# Sheet3_MCU.net
KiCad netlist of a schematic drawn in Altium Designer
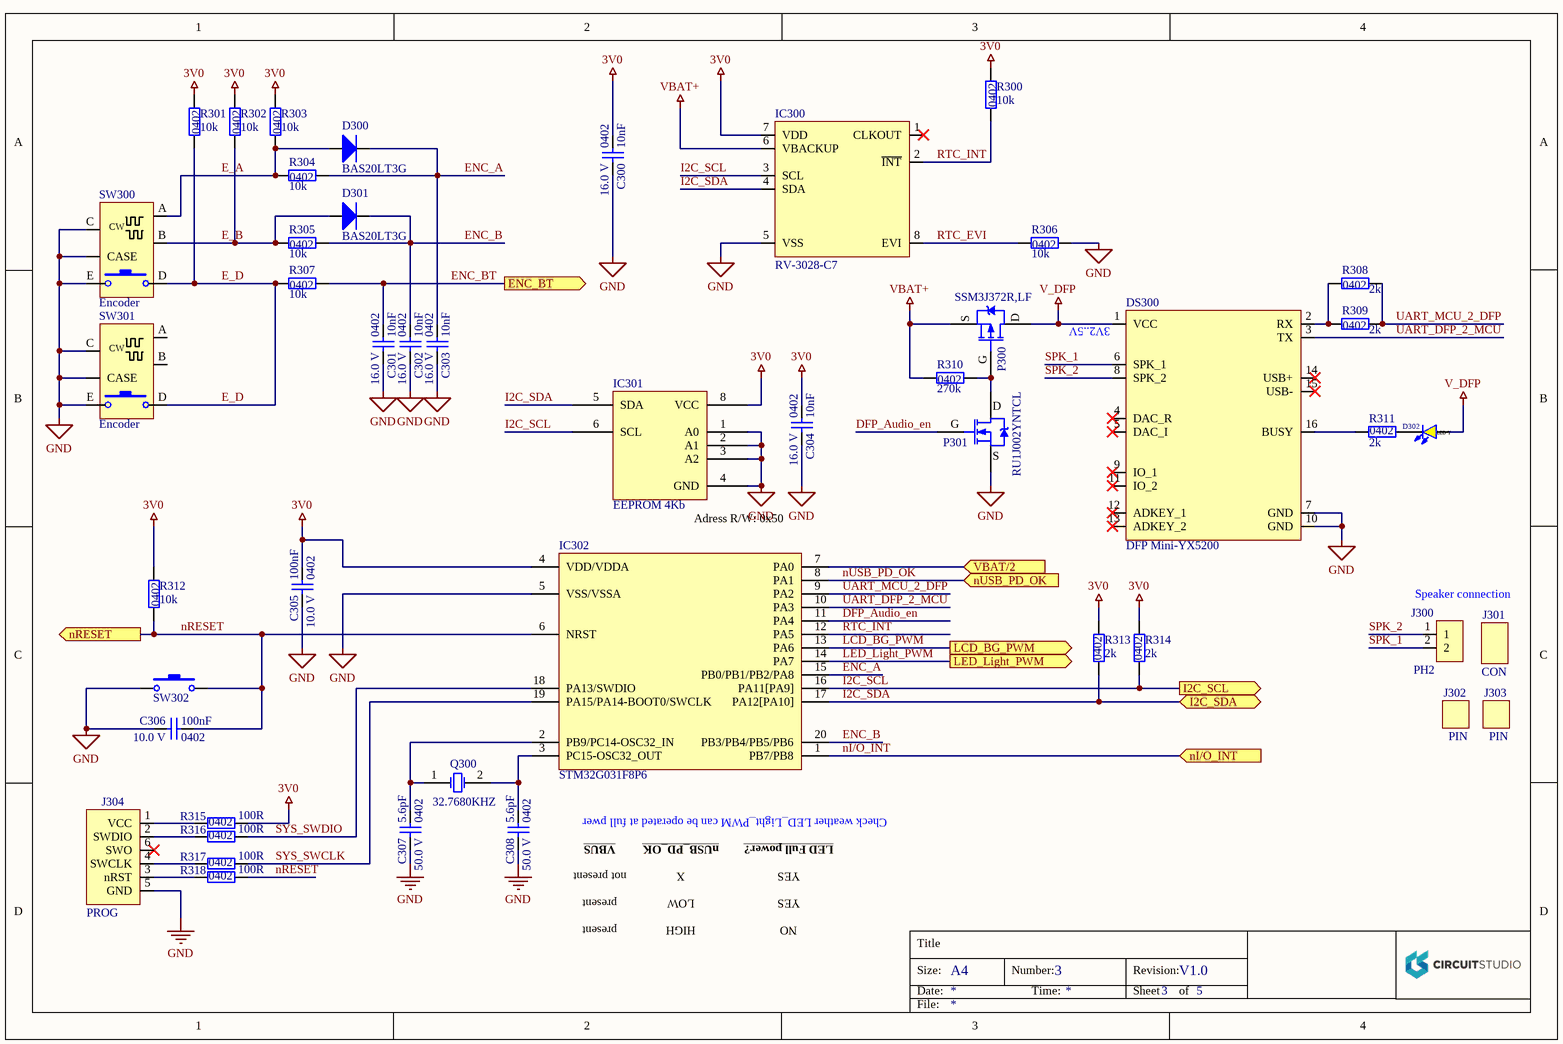
[diagram p0: Sheet3_MCU.SchDoc]

(export (version "E")
  (design (tool "Eeschema 10.0.6"))
  (components
    (comp (ref "C300")
      (value "C 10nF 0402 16V")
      (footprint "0402")
      (description "CAP CER 10000PF 16V Y5V 0402")
      (fields
        (field (name "MANUFACTURER") "Samsung Electro-Mechanics")
        (field (name "MANUFACTURER PART NUMBER") "CL05F103ZO5NNNC")
        (field (name "CAPACITANCE") "10nF")
        (field (name "VOLTAGE") "16.0 V")
      )
      (libsource (lib "CS_Part_Library") (part "CAP_10nF_16V_0402"))
    )
    (comp (ref "C301")
      (value "C 10nF 0402 16V")
      (footprint "0402")
      (description "CAP CER 10000PF 16V Y5V 0402")
      (fields
        (field (name "MANUFACTURER") "Samsung Electro-Mechanics")
        (field (name "MANUFACTURER PART NUMBER") "CL05F103ZO5NNNC")
        (field (name "CAPACITANCE") "10nF")
        (field (name "VOLTAGE") "16.0 V")
      )
      (libsource (lib "CS_Part_Library") (part "CAP_10nF_16V_0402"))
    )
    (comp (ref "C302")
      (value "C 10nF 0402 16V")
      (footprint "0402")
      (description "CAP CER 10000PF 16V Y5V 0402")
      (fields
        (field (name "MANUFACTURER") "Samsung Electro-Mechanics")
        (field (name "MANUFACTURER PART NUMBER") "CL05F103ZO5NNNC")
        (field (name "CAPACITANCE") "10nF")
        (field (name "VOLTAGE") "16.0 V")
      )
      (libsource (lib "CS_Part_Library") (part "CAP_10nF_16V_0402"))
    )
    (comp (ref "C303")
      (value "C 10nF 0402 16V")
      (footprint "0402")
      (description "CAP CER 10000PF 16V Y5V 0402")
      (fields
        (field (name "MANUFACTURER") "Samsung Electro-Mechanics")
        (field (name "MANUFACTURER PART NUMBER") "CL05F103ZO5NNNC")
        (field (name "CAPACITANCE") "10nF")
        (field (name "VOLTAGE") "16.0 V")
      )
      (libsource (lib "CS_Part_Library") (part "CAP_10nF_16V_0402"))
    )
    (comp (ref "C304")
      (value "C 10nF 0402 16V")
      (footprint "0402")
      (description "CAP CER 10000PF 16V Y5V 0402")
      (fields
        (field (name "MANUFACTURER") "Samsung Electro-Mechanics")
        (field (name "MANUFACTURER PART NUMBER") "CL05F103ZO5NNNC")
        (field (name "CAPACITANCE") "10nF")
        (field (name "VOLTAGE") "16.0 V")
      )
      (libsource (lib "CS_Part_Library") (part "CAP_10nF_16V_0402"))
    )
    (comp (ref "C305")
      (value "C 100nF 0402 10V")
      (footprint "0402")
      (description "CAP CER 0.1UF 10V X5R 0402")
      (fields
        (field (name "MANUFACTURER") "Samsung Electro-Mechanics")
        (field (name "MANUFACTURER PART NUMBER") "CL05A104MP5NNNC")
        (field (name "CAPACITANCE") "100nF")
        (field (name "VOLTAGE") "10.0 V")
      )
      (libsource (lib "CS_Part_Library") (part "CAP_100nF_10V_0402"))
    )
    (comp (ref "C306")
      (value "C 100nF 0402 10V")
      (footprint "0402")
      (description "CAP CER 0.1UF 10V X5R 0402")
      (fields
        (field (name "MANUFACTURER") "Samsung Electro-Mechanics")
        (field (name "MANUFACTURER PART NUMBER") "CL05A104MP5NNNC")
        (field (name "CAPACITANCE") "100nF")
        (field (name "VOLTAGE") "10.0 V")
      )
      (libsource (lib "CS_Part_Library") (part "CAP_100nF_10V_0402"))
    )
    (comp (ref "C307")
      (value "C 5.6pF 0402 50V")
      (footprint "0402")
      (description "CAP CER 5.6PF 50V C0G/NP0 0402")
      (fields
        (field (name "MANUFACTURER") "Samsung Electro-Mechanics")
        (field (name "MANUFACTURER PART NUMBER") "CL05C5R6DB5NNNC")
        (field (name "CAPACITANCE") "5.6pF")
        (field (name "VOLTAGE") "50.0 V")
      )
      (libsource (lib "CS_Part_Library") (part "CAP_5.6PF_50V_0402"))
    )
    (comp (ref "C308")
      (value "C 5.6pF 0402 50V")
      (footprint "0402")
      (description "CAP CER 5.6PF 50V C0G/NP0 0402")
      (fields
        (field (name "MANUFACTURER") "Samsung Electro-Mechanics")
        (field (name "MANUFACTURER PART NUMBER") "CL05C5R6DB5NNNC")
        (field (name "CAPACITANCE") "5.6pF")
        (field (name "VOLTAGE") "50.0 V")
      )
      (libsource (lib "CS_Part_Library") (part "CAP_5.6PF_50V_0402"))
    )
    (comp (ref "D300")
      (value "BAS20LT3G")
      (footprint "SOT-23-3")
      (description "DIODE GP 200V 200MA SOT23-3")
      (fields (field (name "MANUFACTURER") "onsemi") (field (name "MANUFACTURER PART NUMBER") "BAS20LT3G"))
      (libsource (lib "Symbols") (part "D_LL_200V_200mA"))
    )
    (comp (ref "D301")
      (value "BAS20LT3G")
      (footprint "SOT-23-3")
      (description "DIODE GP 200V 200MA SOT23-3")
      (fields (field (name "MANUFACTURER") "onsemi") (field (name "MANUFACTURER PART NUMBER") "BAS20LT3G"))
      (libsource (lib "Symbols") (part "D_LL_200V_200mA"))
    )
    (comp (ref "D302")
      (value "LED Y")
      (footprint "LED_0603")
      (description "LED YELLOW DIFFUSED")
      (fields
        (field (name "MANUFACTURER") "Stanley Electric Co")
        (field (name "MANUFACTURER PART NUMBER") "FKY1111C-TR")
      )
      (libsource (lib "CS_Part_Library") (part "D_LED_Yellow_0603"))
    )
    (comp (ref "DS300")
      (value "DFP Mini-YX5200")
      (footprint "DFP_Player_Mini")
      (description "Mini-YX5200 Audio MP3 Modul")
      (fields (field (name "MANUFACTURER") "DFRobot") (field (name "MANUFACTURER PART NUMBER") "DFR0299"))
      (libsource (lib "CS_Part_Library") (part "DFP_Player_mini"))
    )
    (comp (ref "IC300")
      (value "RV-3028-C7")
      (footprint "MC-C7")
      (description "IC RTC CLK/CALENDAR I2C 10SON")
      (fields
        (field (name "MANUFACTURER") "Micro Crystal AG")
        (field (name "MANUFACTURER PART NUMBER") "RV-3028-C7TAQC")
      )
      (libsource (lib "Symbols") (part "IC_RTC_3028-C7"))
    )
    (comp (ref "IC301")
      (value "EEPROM 4Kb")
      (footprint "TSSOP-8_4.4mm")
      (description "IC EEPROM 4KBIT I2C 1MHZ 8TSSOP")
      (fields
        (field (name "MANUFACTURER") "Microchip Technology")
        (field (name "MANUFACTURER PART NUMBER") "AT34C04-X5M-T")
      )
      (libsource (lib "CS_Part_Library") (part "IC_EEPROM_4Kb"))
    )
    (comp (ref "IC302")
      (value "STM32G031F8P6")
      (footprint "TSSOP-20")
      (description "IC MCU 32BIT 32KB FLASH 20TSSOP")
      (fields (field (name "MANUFACTURER") "STMicroelectronics"))
      (libsource (lib "CS_Part_Library") (part "IC_MCU_STM32G031F8P6"))
    )
    (comp (ref "J300")
      (value "PH2")
      (footprint "J_S2B-PH-K-S")
      (description "CONN HEADER R/A 2POS 2MM")
      (fields
        (field (name "MANUFACTURER") "JST Sales America Inc.")
        (field (name "MANUFACTURER PART NUMBER") "S2B-PH-KL(LF)(SN)")
      )
      (libsource (lib "Symbols") (part "J_S2B-PH-KL"))
    )
    (comp (ref "J301")
      (value "CON")
      (description "CONN CONNECTOR PH 2POS 2MM")
      (fields
        (field (name "MANUFACTURER") "JST Sales America Inc.")
        (field (name "MANUFACTURER PART NUMBER") "PHR-2-R")
      )
      (libsource (lib "Symbols") (part "J_PHR-2-R"))
    )
    (comp (ref "J302")
      (value "PIN")
      (description "PIN INSERT")
      (fields
        (field (name "MANUFACTURER") "JST Sales America Inc.")
        (field (name "MANUFACTURER PART NUMBER") "SPH-004T-P0.5S")
      )
      (libsource (lib "Symbols") (part "J_PHR-2-R_PIN"))
    )
    (comp (ref "J303")
      (value "PIN")
      (description "PIN INSERT")
      (fields
        (field (name "MANUFACTURER") "JST Sales America Inc.")
        (field (name "MANUFACTURER PART NUMBER") "SPH-004T-P0.5S")
      )
      (libsource (lib "Symbols") (part "J_PHR-2-R_PIN"))
    )
    (comp (ref "J304")
      (value "PROG")
      (footprint "J_TC2030-IDC-NL")
      (description "SWD Programmer No Legs")
      (fields (field (name "MANUFACTURER") "Tag_connect") (field (name "MANUFACTURER PART NUMBER") "TC2030"))
      (libsource (lib "CS_Part_Library") (part "J_TC2030-IDC-NL"))
    )
    (comp (ref "P300")
      (value "P PMOS 30V 6A")
      (footprint "SOT-23-3-F")
      (description "MOSFET P-CH 30V 6A SOT23F")
      (fields
        (field (name "MANUFACTURER") "Toshiba Semiconductor and Storage")
        (field (name "MANUFACTURER PART NUMBER") "SSM3J372R,LF")
      )
      (libsource (lib "CS_Part_Library") (part "P_PCH_30V_1W"))
    )
    (comp (ref "P301")
      (value "P_NCH_50V_150mW")
      (footprint "UMT3F")
      (description "MOSFET N-CH 50V 200MA UMT3F")
      (fields
        (field (name "MANUFACTURER") "Rohm Semiconductor")
        (field (name "MANUFACTURER PART NUMBER") "RU1J002YNTCL")
      )
      (libsource (lib "CS_Part_Library") (part "P_NCH_50V_150mW"))
    )
    (comp (ref "Q300")
      (value "32.7680KHZ")
      (footprint "Q2_3.2x1.5")
      (description "CRYSTAL 32.7680KHZ 12.5PF SMD")
      (fields
        (field (name "MANUFACTURER") "NDK America, Inc.")
        (field (name "MANUFACTURER PART NUMBER") "NX3215SA-32.768K-EXS00A-MU00003")
      )
      (libsource (lib "CS_Part_Library") (part "Q_32k768_12p5"))
    )
    (comp (ref "R300")
      (value "R 10k 0402")
      (footprint "0402")
      (description "RES 10K OHM 1% 1/16W 0402")
      (fields
        (field (name "MANUFACTURER") "YAGEO")
        (field (name "MANUFACTURER PART NUMBER") "RC0402FR-0710KL")
        (field (name "RESISTANCE") "10k")
      )
      (libsource (lib "CS_Part_Library") (part "R_10k_0402"))
    )
    (comp (ref "R301")
      (value "R 10k 0402")
      (footprint "0402")
      (description "RES 10K OHM 1% 1/16W 0402")
      (fields
        (field (name "MANUFACTURER") "YAGEO")
        (field (name "MANUFACTURER PART NUMBER") "RC0402FR-0710KL")
        (field (name "RESISTANCE") "10k")
      )
      (libsource (lib "CS_Part_Library") (part "R_10k_0402"))
    )
    (comp (ref "R302")
      (value "R 10k 0402")
      (footprint "0402")
      (description "RES 10K OHM 1% 1/16W 0402")
      (fields
        (field (name "MANUFACTURER") "YAGEO")
        (field (name "MANUFACTURER PART NUMBER") "RC0402FR-0710KL")
        (field (name "RESISTANCE") "10k")
      )
      (libsource (lib "CS_Part_Library") (part "R_10k_0402"))
    )
    (comp (ref "R303")
      (value "R 10k 0402")
      (footprint "0402")
      (description "RES 10K OHM 1% 1/16W 0402")
      (fields
        (field (name "MANUFACTURER") "YAGEO")
        (field (name "MANUFACTURER PART NUMBER") "RC0402FR-0710KL")
        (field (name "RESISTANCE") "10k")
      )
      (libsource (lib "CS_Part_Library") (part "R_10k_0402"))
    )
    (comp (ref "R304")
      (value "R 10k 0402")
      (footprint "0402")
      (description "RES 10K OHM 1% 1/16W 0402")
      (fields
        (field (name "MANUFACTURER") "YAGEO")
        (field (name "MANUFACTURER PART NUMBER") "RC0402FR-0710KL")
        (field (name "RESISTANCE") "10k")
      )
      (libsource (lib "") (part "R_10k_0402_1"))
    )
    (comp (ref "R305")
      (value "R 10k 0402")
      (footprint "0402")
      (description "RES 10K OHM 1% 1/16W 0402")
      (fields
        (field (name "MANUFACTURER") "YAGEO")
        (field (name "MANUFACTURER PART NUMBER") "RC0402FR-0710KL")
        (field (name "RESISTANCE") "10k")
      )
      (libsource (lib "") (part "R_10k_0402_1"))
    )
    (comp (ref "R306")
      (value "R 10k 0402")
      (footprint "0402")
      (description "RES 10K OHM 1% 1/16W 0402")
      (fields
        (field (name "MANUFACTURER") "YAGEO")
        (field (name "MANUFACTURER PART NUMBER") "RC0402FR-0710KL")
        (field (name "RESISTANCE") "10k")
      )
      (libsource (lib "") (part "R_10k_0402_1"))
    )
    (comp (ref "R307")
      (value "R 10k 0402")
      (footprint "0402")
      (description "RES 10K OHM 1% 1/16W 0402")
      (fields
        (field (name "MANUFACTURER") "YAGEO")
        (field (name "MANUFACTURER PART NUMBER") "RC0402FR-0710KL")
        (field (name "RESISTANCE") "10k")
      )
      (libsource (lib "") (part "R_10k_0402_1"))
    )
    (comp (ref "R308")
      (value "R 2k 0402")
      (footprint "0402")
      (description "RES 2K OHM 1% 1/16W 0402")
      (fields
        (field (name "MANUFACTURER") "Stackpole Electronics Inc")
        (field (name "MANUFACTURER PART NUMBER") "RMCF0402FT2K00")
        (field (name "RESISTANCE") "2k")
      )
      (libsource (lib "CS_Part_Library") (part "R_2k_0402"))
    )
    (comp (ref "R309")
      (value "R 2k 0402")
      (footprint "0402")
      (description "RES 2K OHM 1% 1/16W 0402")
      (fields
        (field (name "MANUFACTURER") "Stackpole Electronics Inc")
        (field (name "MANUFACTURER PART NUMBER") "RMCF0402FT2K00")
        (field (name "RESISTANCE") "2k")
      )
      (libsource (lib "CS_Part_Library") (part "R_2k_0402"))
    )
    (comp (ref "R310")
      (value "R 270k 0402")
      (footprint "0402")
      (description "RES 270K OHM 1% 1/16W 0402")
      (fields
        (field (name "MANUFACTURER") "YAGEO")
        (field (name "MANUFACTURER PART NUMBER") "RC0402FR-07270KL")
        (field (name "RESISTANCE") "270k")
      )
      (libsource (lib "CS_Part_Library") (part "R_270k_0402"))
    )
    (comp (ref "R311")
      (value "R 2k 0402")
      (footprint "0402")
      (description "RES 2K OHM 1% 1/16W 0402")
      (fields
        (field (name "MANUFACTURER") "Stackpole Electronics Inc")
        (field (name "MANUFACTURER PART NUMBER") "RMCF0402FT2K00")
        (field (name "RESISTANCE") "2k")
      )
      (libsource (lib "") (part "R_2k_0402_1"))
    )
    (comp (ref "R312")
      (value "R 10k 0402")
      (footprint "0402")
      (description "RES 10K OHM 1% 1/16W 0402")
      (fields
        (field (name "MANUFACTURER") "YAGEO")
        (field (name "MANUFACTURER PART NUMBER") "RC0402FR-0710KL")
        (field (name "RESISTANCE") "10k")
      )
      (libsource (lib "CS_Part_Library") (part "R_10k_0402"))
    )
    (comp (ref "R313")
      (value "R 2k 0402")
      (footprint "0402")
      (description "RES 2K OHM 1% 1/16W 0402")
      (fields
        (field (name "MANUFACTURER") "Stackpole Electronics Inc")
        (field (name "MANUFACTURER PART NUMBER") "RMCF0402FT2K00")
        (field (name "RESISTANCE") "2k")
      )
      (libsource (lib "") (part "R_2k_0402_2"))
    )
    (comp (ref "R314")
      (value "R 2k 0402")
      (footprint "0402")
      (description "RES 2K OHM 1% 1/16W 0402")
      (fields
        (field (name "MANUFACTURER") "Stackpole Electronics Inc")
        (field (name "MANUFACTURER PART NUMBER") "RMCF0402FT2K00")
        (field (name "RESISTANCE") "2k")
      )
      (libsource (lib "") (part "R_2k_0402_2"))
    )
    (comp (ref "R315")
      (value "R 100R 0402")
      (footprint "0402")
      (description "RES 100 OHM 1% 1/16W 0402")
      (fields
        (field (name "MANUFACTURER") "Stackpole Electronics Inc")
        (field (name "MANUFACTURER PART NUMBER") "RMCF0402FT100R")
        (field (name "RESISTANCE") "100R")
      )
      (libsource (lib "Symbols") (part "R_100R_0402"))
    )
    (comp (ref "R316")
      (value "R 100R 0402")
      (footprint "0402")
      (description "RES 100 OHM 1% 1/16W 0402")
      (fields
        (field (name "MANUFACTURER") "Stackpole Electronics Inc")
        (field (name "MANUFACTURER PART NUMBER") "RMCF0402FT100R")
        (field (name "RESISTANCE") "100R")
      )
      (libsource (lib "Symbols") (part "R_100R_0402"))
    )
    (comp (ref "R317")
      (value "R 100R 0402")
      (footprint "0402")
      (description "RES 100 OHM 1% 1/16W 0402")
      (fields
        (field (name "MANUFACTURER") "Stackpole Electronics Inc")
        (field (name "MANUFACTURER PART NUMBER") "RMCF0402FT100R")
        (field (name "RESISTANCE") "100R")
      )
      (libsource (lib "Symbols") (part "R_100R_0402"))
    )
    (comp (ref "R318")
      (value "R 100R 0402")
      (footprint "0402")
      (description "RES 100 OHM 1% 1/16W 0402")
      (fields
        (field (name "MANUFACTURER") "Stackpole Electronics Inc")
        (field (name "MANUFACTURER PART NUMBER") "RMCF0402FT100R")
        (field (name "RESISTANCE") "100R")
      )
      (libsource (lib "Symbols") (part "R_100R_0402"))
    )
    (comp (ref "SW300")
      (value "Encoder")
      (footprint "PEC11R")
      (description "ROTARY ENCODER MECHANICAL 12PPR")
      (fields
        (field (name "MANUFACTURER") "Bourns Inc.")
        (field (name "MANUFACTURER PART NUMBER") "PEC11R-4220F-S0012")
      )
      (libsource (lib "CS_Part_Library") (part "ENC_12_THT"))
    )
    (comp (ref "SW301")
      (value "Encoder")
      (footprint "PEC11R")
      (description "ROTARY ENCODER MECHANICAL 12PPR")
      (fields
        (field (name "MANUFACTURER") "Bourns Inc.")
        (field (name "MANUFACTURER PART NUMBER") "PEC11R-4220F-S0012")
      )
      (libsource (lib "CS_Part_Library") (part "ENC_12_THT"))
    )
    (comp (ref "SW302")
      (value "SW")
      (footprint "SW_PTS810")
      (description "SWITCH TACTILE SPST-NO 0.05A 16V")
      (fields
        (field (name "MANUFACTURER") "C&K")
        (field (name "MANUFACTURER PART NUMBER") "PTS810 SJM 250 SMTR LFS")
      )
      (libsource (lib "CS_Part_Library") (part "SW_TactileSW_V"))
    )
  )
  (nets
    (net (code "1") (name "/DFP_Audio_en") (class "Default")
      (node (ref "IC302") (pin "11") (pinfunction "PA4_11") (pintype "passive"))
      (node (ref "P301") (pin "1") (pinfunction "G_1") (pintype "passive"))
    )
    (net (code "2") (name "/ENC_A") (class "Default")
      (node (ref "C303") (pin "2") (pinfunction "2_2") (pintype "passive"))
      (node (ref "D300") (pin "3") (pinfunction "K_3") (pintype "passive"))
      (node (ref "IC302") (pin "15") (pinfunction "PB0/PB1/PB2/PA8_15") (pintype "passive"))
      (node (ref "R304") (pin "2") (pinfunction "2_2") (pintype "passive"))
    )
    (net (code "3") (name "/ENC_B") (class "Default")
      (node (ref "C302") (pin "2") (pinfunction "2_2") (pintype "passive"))
      (node (ref "D301") (pin "3") (pinfunction "K_3") (pintype "passive"))
      (node (ref "IC302") (pin "20") (pinfunction "PB3/PB4/PB5/PB6_20") (pintype "passive"))
      (node (ref "R305") (pin "2") (pinfunction "2_2") (pintype "passive"))
    )
    (net (code "4") (name "/ENC_BT") (class "Default")
      (node (ref "C301") (pin "2") (pinfunction "2_2") (pintype "passive"))
      (node (ref "R307") (pin "2") (pinfunction "2_2") (pintype "passive"))
    )
    (net (code "5") (name "/E_A") (class "Default")
      (node (ref "D300") (pin "1") (pinfunction "A_1") (pintype "passive"))
      (node (ref "R303") (pin "1") (pinfunction "1_1") (pintype "passive"))
      (node (ref "R304") (pin "1") (pinfunction "1_1") (pintype "passive"))
      (node (ref "SW300") (pin "A") (pinfunction "A_A") (pintype "passive"))
    )
    (net (code "6") (name "/E_B") (class "Default")
      (node (ref "D301") (pin "1") (pinfunction "A_1") (pintype "passive"))
      (node (ref "R302") (pin "1") (pinfunction "1_1") (pintype "passive"))
      (node (ref "R305") (pin "1") (pinfunction "1_1") (pintype "passive"))
      (node (ref "SW300") (pin "B") (pinfunction "B_B") (pintype "passive"))
    )
    (net (code "7") (name "/E_D") (class "Default")
      (node (ref "R301") (pin "1") (pinfunction "1_1") (pintype "passive"))
      (node (ref "R307") (pin "1") (pinfunction "1_1") (pintype "passive"))
      (node (ref "SW300") (pin "D") (pinfunction "D_D") (pintype "passive"))
      (node (ref "SW301") (pin "D") (pinfunction "D_D") (pintype "passive"))
    )
    (net (code "8") (name "/I2C_SCL") (class "Default")
      (node (ref "IC300") (pin "3") (pinfunction "SCL_3") (pintype "passive"))
      (node (ref "IC301") (pin "6") (pinfunction "SCL_6") (pintype "passive"))
      (node (ref "IC302") (pin "16") (pinfunction "PA11[PA9]_16") (pintype "passive"))
      (node (ref "R314") (pin "1") (pinfunction "1_1") (pintype "passive"))
    )
    (net (code "9") (name "/I2C_SDA") (class "Default")
      (node (ref "IC300") (pin "4") (pinfunction "SDA_4") (pintype "passive"))
      (node (ref "IC301") (pin "5") (pinfunction "SDA_5") (pintype "passive"))
      (node (ref "IC302") (pin "17") (pinfunction "PA12[PA10]_17") (pintype "passive"))
      (node (ref "R313") (pin "1") (pinfunction "1_1") (pintype "passive"))
    )
    (net (code "10") (name "/LCD_BG_PWM") (class "Default")
      (node (ref "IC302") (pin "13") (pinfunction "PA6_13") (pintype "passive"))
    )
    (net (code "11") (name "/LED_Light_PWM") (class "Default")
      (node (ref "IC302") (pin "14") (pinfunction "PA7_14") (pintype "passive"))
    )
    (net (code "12") (name "/RTC_EVI") (class "Default")
      (node (ref "IC300") (pin "8") (pinfunction "EVI_8") (pintype "passive"))
      (node (ref "R306") (pin "1") (pinfunction "1_1") (pintype "passive"))
    )
    (net (code "13") (name "/RTC_INT") (class "Default")
      (node (ref "IC300") (pin "2") (pinfunction "~{INT}_2") (pintype "passive"))
      (node (ref "IC302") (pin "12") (pinfunction "PA5_12") (pintype "passive"))
      (node (ref "R300") (pin "1") (pinfunction "1_1") (pintype "passive"))
    )
    (net (code "14") (name "/SPK_1") (class "Default")
      (node (ref "DS300") (pin "6") (pinfunction "SPK_1_6") (pintype "passive"))
      (node (ref "J300") (pin "2") (pinfunction "2_2") (pintype "passive"))
    )
    (net (code "15") (name "/SPK_2") (class "Default")
      (node (ref "DS300") (pin "8") (pinfunction "SPK_2_8") (pintype "passive"))
      (node (ref "J300") (pin "1") (pinfunction "1_1") (pintype "passive"))
    )
    (net (code "16") (name "/SYS_SWCLK") (class "Default")
      (node (ref "IC302") (pin "19") (pinfunction "PA15/PA14-BOOT0/SWCLK_19") (pintype "passive"))
      (node (ref "R317") (pin "2") (pinfunction "2_2") (pintype "passive"))
    )
    (net (code "17") (name "/SYS_SWDIO") (class "Default")
      (node (ref "IC302") (pin "18") (pinfunction "PA13/SWDIO_18") (pintype "passive"))
      (node (ref "R316") (pin "2") (pinfunction "2_2") (pintype "passive"))
    )
    (net (code "18") (name "/UART_DFP_2_MCU") (class "Default")
      (node (ref "DS300") (pin "3") (pinfunction "TX_3") (pintype "passive"))
      (node (ref "IC302") (pin "10") (pinfunction "PA3_10") (pintype "passive"))
    )
    (net (code "19") (name "/UART_MCU_2_DFP") (class "Default")
      (node (ref "IC302") (pin "9") (pinfunction "PA2_9") (pintype "passive"))
      (node (ref "R308") (pin "1") (pinfunction "1_1") (pintype "passive"))
      (node (ref "R309") (pin "1") (pinfunction "1_1") (pintype "passive"))
    )
    (net (code "20") (name "/VBAT{slash}2") (class "Default")
      (node (ref "IC302") (pin "7") (pinfunction "PA0_7") (pintype "passive"))
    )
    (net (code "21") (name "/nI{slash}O_INT") (class "Default")
      (node (ref "IC302") (pin "1") (pinfunction "PB7/PB8_1") (pintype "passive"))
    )
    (net (code "22") (name "/nRESET") (class "Default")
      (node (ref "C306") (pin "2") (pinfunction "2_2") (pintype "passive"))
      (node (ref "IC302") (pin "6") (pinfunction "NRST_6") (pintype "passive"))
      (node (ref "R312") (pin "1") (pinfunction "1_1") (pintype "passive"))
      (node (ref "R318") (pin "2") (pinfunction "2_2") (pintype "passive"))
      (node (ref "SW302") (pin "3") (pinfunction "2,_3_3") (pintype "passive"))
    )
    (net (code "23") (name "/nUSB_PD_OK") (class "Default")
      (node (ref "IC302") (pin "8") (pinfunction "PA1_8") (pintype "passive"))
    )
    (net (code "24") (name "3V0") (class "Default")
      (node (ref "C300") (pin "2") (pinfunction "2_2") (pintype "passive"))
      (node (ref "C304") (pin "2") (pinfunction "2_2") (pintype "passive"))
      (node (ref "C305") (pin "2") (pinfunction "2_2") (pintype "passive"))
      (node (ref "IC300") (pin "7") (pinfunction "VDD_7") (pintype "passive"))
      (node (ref "IC301") (pin "8") (pinfunction "VCC_8") (pintype "passive"))
      (node (ref "IC302") (pin "4") (pinfunction "VDD/VDDA_4") (pintype "passive"))
      (node (ref "R300") (pin "2") (pinfunction "2_2") (pintype "passive"))
      (node (ref "R301") (pin "2") (pinfunction "2_2") (pintype "passive"))
      (node (ref "R302") (pin "2") (pinfunction "2_2") (pintype "passive"))
      (node (ref "R303") (pin "2") (pinfunction "2_2") (pintype "passive"))
      (node (ref "R312") (pin "2") (pinfunction "2_2") (pintype "passive"))
      (node (ref "R313") (pin "2") (pinfunction "2_2") (pintype "passive"))
      (node (ref "R314") (pin "2") (pinfunction "2_2") (pintype "passive"))
      (node (ref "R315") (pin "2") (pinfunction "2_2") (pintype "passive"))
    )
    (net (code "25") (name "GND") (class "Default")
      (node (ref "C300") (pin "1") (pinfunction "1_1") (pintype "passive"))
      (node (ref "C301") (pin "1") (pinfunction "1_1") (pintype "passive"))
      (node (ref "C302") (pin "1") (pinfunction "1_1") (pintype "passive"))
      (node (ref "C303") (pin "1") (pinfunction "1_1") (pintype "passive"))
      (node (ref "C304") (pin "1") (pinfunction "1_1") (pintype "passive"))
      (node (ref "C305") (pin "1") (pinfunction "1_1") (pintype "passive"))
      (node (ref "C306") (pin "1") (pinfunction "1_1") (pintype "passive"))
      (node (ref "C307") (pin "1") (pinfunction "1_1") (pintype "passive"))
      (node (ref "C308") (pin "1") (pinfunction "1_1") (pintype "passive"))
      (node (ref "DS300") (pin "10") (pinfunction "GND_10") (pintype "passive"))
      (node (ref "DS300") (pin "7") (pinfunction "GND_7") (pintype "passive"))
      (node (ref "IC300") (pin "5") (pinfunction "VSS_5") (pintype "passive"))
      (node (ref "IC301") (pin "1") (pinfunction "A0_1") (pintype "passive"))
      (node (ref "IC301") (pin "2") (pinfunction "A1_2") (pintype "passive"))
      (node (ref "IC301") (pin "3") (pinfunction "A2_3") (pintype "passive"))
      (node (ref "IC301") (pin "4") (pinfunction "GND_4") (pintype "passive"))
      (node (ref "IC302") (pin "5") (pinfunction "VSS/VSSA_5") (pintype "passive"))
      (node (ref "J304") (pin "5") (pinfunction "GND_5") (pintype "passive"))
      (node (ref "P301") (pin "2") (pinfunction "S_2") (pintype "passive"))
      (node (ref "R306") (pin "2") (pinfunction "2_2") (pintype "passive"))
      (node (ref "SW300") (pin "C") (pinfunction "C_C") (pintype "passive"))
      (node (ref "SW300") (pin "CASE") (pinfunction "CASE_CASE") (pintype "passive"))
      (node (ref "SW300") (pin "E") (pinfunction "E_E") (pintype "passive"))
      (node (ref "SW301") (pin "C") (pinfunction "C_C") (pintype "passive"))
      (node (ref "SW301") (pin "CASE") (pinfunction "CASE_CASE") (pintype "passive"))
      (node (ref "SW301") (pin "E") (pinfunction "E_E") (pintype "passive"))
      (node (ref "SW302") (pin "1") (pinfunction "1,_2_1") (pintype "passive"))
    )
    (net (code "26") (name "Net-(D302-PadK)") (class "Default")
      (node (ref "D302") (pin "K") (pinfunction "K_K") (pintype "passive"))
      (node (ref "R311") (pin "2") (pinfunction "2_2") (pintype "passive"))
    )
    (net (code "27") (name "Net-(DS300-BUSY)") (class "Default")
      (node (ref "DS300") (pin "16") (pinfunction "BUSY_16") (pintype "passive"))
      (node (ref "R311") (pin "1") (pinfunction "1_1") (pintype "passive"))
    )
    (net (code "28") (name "Net-(DS300-RX)") (class "Default")
      (node (ref "DS300") (pin "2") (pinfunction "RX_2") (pintype "passive"))
      (node (ref "R308") (pin "2") (pinfunction "2_2") (pintype "passive"))
      (node (ref "R309") (pin "2") (pinfunction "2_2") (pintype "passive"))
    )
    (net (code "29") (name "Net-(IC302-PB9{slash}PC14-OSC32_IN)") (class "Default")
      (node (ref "C307") (pin "2") (pinfunction "2_2") (pintype "passive"))
      (node (ref "IC302") (pin "2") (pinfunction "PB9/PC14-OSC32_IN_2") (pintype "passive"))
      (node (ref "Q300") (pin "1") (pinfunction "OSC1_1") (pintype "passive"))
    )
    (net (code "30") (name "Net-(IC302-PC15-OSC32_OUT)") (class "Default")
      (node (ref "C308") (pin "2") (pinfunction "2_2") (pintype "passive"))
      (node (ref "IC302") (pin "3") (pinfunction "PC15-OSC32_OUT_3") (pintype "passive"))
      (node (ref "Q300") (pin "2") (pinfunction "OSC2_2") (pintype "passive"))
    )
    (net (code "31") (name "Net-(J304-SWCLK)") (class "Default")
      (node (ref "J304") (pin "4") (pinfunction "SWCLK_4") (pintype "passive"))
      (node (ref "R317") (pin "1") (pinfunction "1_1") (pintype "passive"))
    )
    (net (code "32") (name "Net-(J304-SWDIO)") (class "Default")
      (node (ref "J304") (pin "2") (pinfunction "SWDIO_2") (pintype "passive"))
      (node (ref "R316") (pin "1") (pinfunction "1_1") (pintype "passive"))
    )
    (net (code "33") (name "Net-(J304-VCC)") (class "Default")
      (node (ref "J304") (pin "1") (pinfunction "VCC_1") (pintype "passive"))
      (node (ref "R315") (pin "1") (pinfunction "1_1") (pintype "passive"))
    )
    (net (code "34") (name "Net-(J304-nRST)") (class "Default")
      (node (ref "J304") (pin "3") (pinfunction "nRST_3") (pintype "passive"))
      (node (ref "R318") (pin "1") (pinfunction "1_1") (pintype "passive"))
    )
    (net (code "35") (name "Net-(P300-G)") (class "Default")
      (node (ref "P300") (pin "1") (pinfunction "G_1") (pintype "passive"))
      (node (ref "P301") (pin "3") (pinfunction "D_3") (pintype "passive"))
      (node (ref "R310") (pin "1") (pinfunction "1_1") (pintype "passive"))
    )
    (net (code "36") (name "VBAT+") (class "Default")
      (node (ref "IC300") (pin "6") (pinfunction "VBACKUP_6") (pintype "passive"))
      (node (ref "P300") (pin "2") (pinfunction "S_2") (pintype "passive"))
      (node (ref "R310") (pin "2") (pinfunction "2_2") (pintype "passive"))
    )
    (net (code "37") (name "V_DFP") (class "Default")
      (node (ref "D302") (pin "A") (pinfunction "A_A") (pintype "passive"))
      (node (ref "DS300") (pin "1") (pinfunction "VCC_1") (pintype "passive"))
      (node (ref "P300") (pin "3") (pinfunction "D_3") (pintype "passive"))
    )
    (net (code "38") (name "unconnected-(DS300-ADKEY_1-Pad12)") (class "Default")
      (node (ref "DS300") (pin "12") (pinfunction "ADKEY_1_12") (pintype "passive+no_connect"))
    )
    (net (code "39") (name "unconnected-(DS300-ADKEY_2-Pad13)") (class "Default")
      (node (ref "DS300") (pin "13") (pinfunction "ADKEY_2_13") (pintype "passive+no_connect"))
    )
    (net (code "40") (name "unconnected-(DS300-DAC_I-Pad5)") (class "Default")
      (node (ref "DS300") (pin "5") (pinfunction "DAC_I_5") (pintype "passive+no_connect"))
    )
    (net (code "41") (name "unconnected-(DS300-DAC_R-Pad4)") (class "Default")
      (node (ref "DS300") (pin "4") (pinfunction "DAC_R_4") (pintype "passive+no_connect"))
    )
    (net (code "42") (name "unconnected-(DS300-IO_1-Pad9)") (class "Default")
      (node (ref "DS300") (pin "9") (pinfunction "IO_1_9") (pintype "passive+no_connect"))
    )
    (net (code "43") (name "unconnected-(DS300-IO_2-Pad11)") (class "Default")
      (node (ref "DS300") (pin "11") (pinfunction "IO_2_11") (pintype "passive+no_connect"))
    )
    (net (code "44") (name "unconnected-(DS300-USB+-Pad14)") (class "Default")
      (node (ref "DS300") (pin "14") (pinfunction "USB+_14") (pintype "passive+no_connect"))
    )
    (net (code "45") (name "unconnected-(DS300-USB--Pad15)") (class "Default")
      (node (ref "DS300") (pin "15") (pinfunction "USB-_15") (pintype "passive+no_connect"))
    )
    (net (code "46") (name "unconnected-(IC300-CLKOUT-Pad1)") (class "Default")
      (node (ref "IC300") (pin "1") (pinfunction "CLKOUT_1") (pintype "passive+no_connect"))
    )
    (net (code "47") (name "unconnected-(J304-SWO-Pad6)") (class "Default")
      (node (ref "J304") (pin "6") (pinfunction "SWO_6") (pintype "passive+no_connect"))
    )
    (net (code "48") (name "unconnected-(SW301-PadA)") (class "Default")
      (node (ref "SW301") (pin "A") (pinfunction "A_A") (pintype "passive"))
    )
    (net (code "49") (name "unconnected-(SW301-PadB)") (class "Default")
      (node (ref "SW301") (pin "B") (pinfunction "B_B") (pintype "passive"))
    )
  )
)
